# opt2bnc_trigger_1Ch.net
KiCad netlist of a schematic drawn in EAGLE
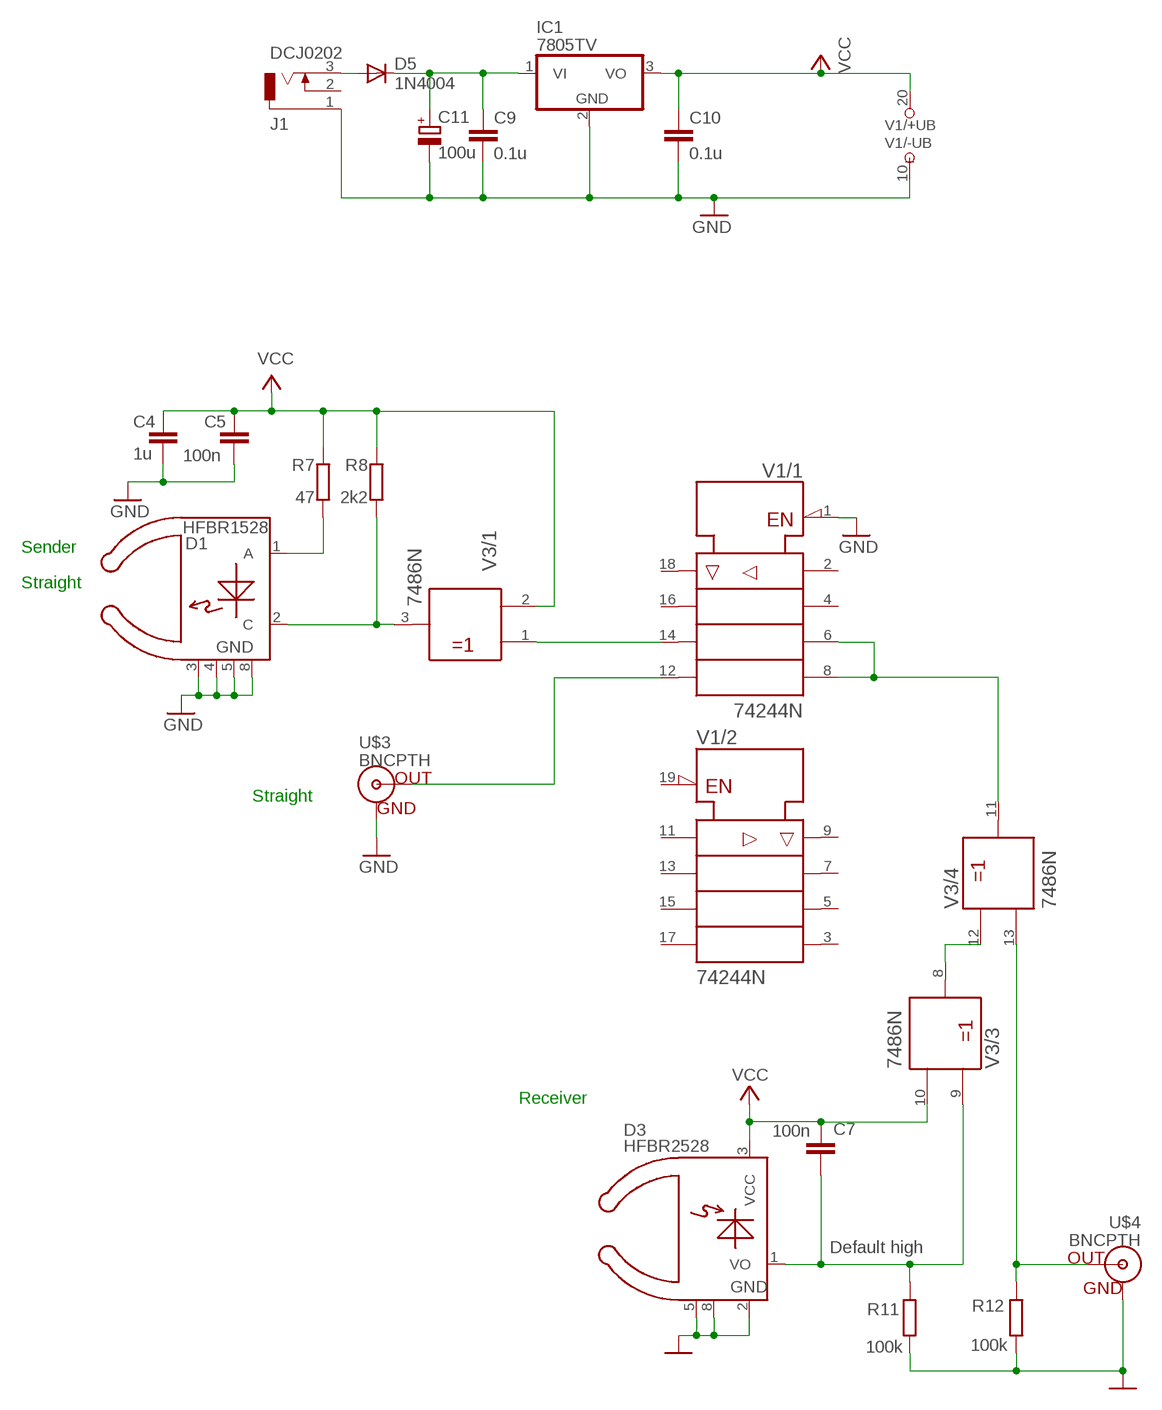
[diagram p0: schematic, sheet 1]

(export (version "E")
  (design (tool "Eeschema 10.0.6"))
  (components
    (comp (ref "C4")
      (value "1u")
      (footprint "eagle-import:C025-025X050")
      (libsource (lib "eagle-import") (part "C-EU025-025X050"))
    )
    (comp (ref "C5")
      (value "100n")
      (footprint "eagle-import:C025-025X050")
      (libsource (lib "eagle-import") (part "C-EU025-025X050"))
    )
    (comp (ref "C7")
      (value "100n")
      (footprint "eagle-import:C025-025X050")
      (libsource (lib "eagle-import") (part "C-EU025-025X050"))
    )
    (comp (ref "C9")
      (value "0.1u")
      (footprint "eagle-import:C025-024X044")
      (libsource (lib "eagle-import") (part "C-EU025-024X044"))
    )
    (comp (ref "C10")
      (value "0.1u")
      (footprint "eagle-import:C025-024X044")
      (libsource (lib "eagle-import") (part "C-EU025-024X044"))
    )
    (comp (ref "C11")
      (value "100u")
      (footprint "eagle-import:E2-4")
      (libsource (lib "eagle-import") (part "CPOL-EUE2-4"))
    )
    (comp (ref "D1")
      (value "HFBR1528")
      (footprint "eagle-import:HFBR25XX")
      (fields (field (name "MF") "AGILENT TECHNOLOGIES") (field (name "MPN") "HFBR-1528"))
      (libsource (lib "eagle-import") (part "HFBR1528"))
    )
    (comp (ref "D3")
      (value "HFBR2528")
      (footprint "eagle-import:HFBR25XX")
      (fields (field (name "MF") "AGILENT TECHNOLOGIES") (field (name "MPN") "HFBR-2528"))
      (libsource (lib "eagle-import") (part "HFBR2528"))
    )
    (comp (ref "D5")
      (value "1N4004")
      (footprint "eagle-import:DO41-10")
      (libsource (lib "eagle-import") (part "1N4004"))
    )
    (comp (ref "IC1")
      (value "7805TV")
      (footprint "eagle-import:TO220V")
      (libsource (lib "eagle-import") (part "78TV05"))
    )
    (comp (ref "J1")
      (value "DCJ0202")
      (footprint "eagle-import:DCJ0202")
      (libsource (lib "eagle-import") (part "DCJ0202"))
    )
    (comp (ref "R7")
      (value "47")
      (footprint "eagle-import:0207_7")
      (libsource (lib "eagle-import") (part "R-EU_0207/7"))
    )
    (comp (ref "R8")
      (value "2k2")
      (footprint "eagle-import:0207_7")
      (libsource (lib "eagle-import") (part "R-EU_0207/7"))
    )
    (comp (ref "R11")
      (value "100k")
      (footprint "eagle-import:0207_7")
      (libsource (lib "eagle-import") (part "R-EU_0207/7"))
    )
    (comp (ref "R12")
      (value "100k")
      (footprint "eagle-import:0207_7")
      (libsource (lib "eagle-import") (part "R-EU_0207/7"))
    )
    (comp (ref "U$3")
      (value "BNCPTH")
      (footprint "eagle-import:BNC")
      (libsource (lib "eagle-import") (part "BNCPTH"))
    )
    (comp (ref "U$4")
      (value "BNCPTH")
      (footprint "eagle-import:BNC")
      (libsource (lib "eagle-import") (part "BNCPTH"))
    )
    (comp (ref "V1")
      (value "74244N")
      (footprint "eagle-import:DIL20")
      (libsource (lib "eagle-import") (part "74244N"))
    )
    (comp (ref "V3")
      (value "7486N")
      (footprint "eagle-import:DIL14")
      (libsource (lib "eagle-import") (part "7486N"))
    )
  )
  (nets
    (net (code "1") (name "GND") (class "Default")
      (node (ref "C10") (pin "2") (pinfunction "2_2") (pintype "passive"))
      (node (ref "C11") (pin "-") (pinfunction "-_-") (pintype "passive"))
      (node (ref "C4") (pin "2") (pinfunction "2_2") (pintype "passive"))
      (node (ref "C5") (pin "2") (pinfunction "2_2") (pintype "passive"))
      (node (ref "C9") (pin "2") (pinfunction "2_2") (pintype "passive"))
      (node (ref "D1") (pin "3") (pinfunction "1_3") (pintype "passive"))
      (node (ref "D1") (pin "4") (pinfunction "4_4") (pintype "passive"))
      (node (ref "D1") (pin "5") (pinfunction "GND_5") (pintype "passive"))
      (node (ref "D1") (pin "8") (pinfunction "GND_8") (pintype "passive"))
      (node (ref "D3") (pin "2") (pinfunction "GND_2") (pintype "passive"))
      (node (ref "D3") (pin "5") (pinfunction "1_5") (pintype "passive"))
      (node (ref "D3") (pin "8") (pinfunction "4_8") (pintype "passive"))
      (node (ref "IC1") (pin "2") (pinfunction "GND_2") (pintype "passive"))
      (node (ref "J1") (pin "1") (pinfunction "1_1") (pintype "passive"))
      (node (ref "R11") (pin "2") (pinfunction "2_2") (pintype "passive"))
      (node (ref "R12") (pin "2") (pinfunction "2_2") (pintype "passive"))
      (node (ref "U$3") (pin "GND") (pinfunction "GND_GND") (pintype "bidirectional"))
      (node (ref "U$4") (pin "GND") (pinfunction "GND_GND") (pintype "bidirectional"))
      (node (ref "V1") (pin "1") (pinfunction "~{G}_1") (pintype "input"))
      (node (ref "V1") (pin "10") (pinfunction "-UB_10") (pintype "power_in"))
    )
    (net (code "2") (name "Net-(D1-A)") (class "Default")
      (node (ref "D1") (pin "1") (pinfunction "A_1") (pintype "passive"))
      (node (ref "R7") (pin "1") (pinfunction "1_1") (pintype "passive"))
    )
    (net (code "3") (name "Net-(D1-C)") (class "Default")
      (node (ref "D1") (pin "2") (pinfunction "C_2") (pintype "passive"))
      (node (ref "R8") (pin "1") (pinfunction "1_1") (pintype "passive"))
      (node (ref "V3") (pin "3") (pinfunction "Y_3") (pintype "output"))
    )
    (net (code "4") (name "Net-(D3-VO)") (class "Default")
      (node (ref "C7") (pin "1") (pinfunction "1_1") (pintype "passive"))
      (node (ref "D3") (pin "1") (pinfunction "VO_1") (pintype "output"))
      (node (ref "R11") (pin "1") (pinfunction "1_1") (pintype "passive"))
      (node (ref "V3") (pin "9") (pinfunction "A_9") (pintype "input"))
    )
    (net (code "5") (name "Net-(D5-PadA)") (class "Default")
      (node (ref "D5") (pin "A") (pinfunction "A_A") (pintype "passive"))
      (node (ref "J1") (pin "3") (pinfunction "3_3") (pintype "passive"))
    )
    (net (code "6") (name "Net-(IC1-VI)") (class "Default")
      (node (ref "C11") (pin "+") (pinfunction "+_+") (pintype "passive"))
      (node (ref "C9") (pin "1") (pinfunction "1_1") (pintype "passive"))
      (node (ref "D5") (pin "C") (pinfunction "C_C") (pintype "passive"))
      (node (ref "IC1") (pin "1") (pinfunction "VI_1") (pintype "input"))
    )
    (net (code "7") (name "Net-(U$3-OUT)") (class "Default")
      (node (ref "U$3") (pin "S") (pinfunction "OUT_S") (pintype "bidirectional"))
      (node (ref "V1") (pin "12") (pinfunction "Y4_12") (pintype "tri_state"))
    )
    (net (code "8") (name "Net-(U$4-OUT)") (class "Default")
      (node (ref "R12") (pin "1") (pinfunction "1_1") (pintype "passive"))
      (node (ref "U$4") (pin "S") (pinfunction "OUT_S") (pintype "bidirectional"))
      (node (ref "V3") (pin "13") (pinfunction "B_13") (pintype "input"))
    )
    (net (code "9") (name "Net-(V1C-A3)") (class "Default")
      (node (ref "V1") (pin "6") (pinfunction "A3_6") (pintype "input"))
      (node (ref "V1") (pin "8") (pinfunction "A4_8") (pintype "input"))
      (node (ref "V3") (pin "11") (pinfunction "Y_11") (pintype "output"))
    )
    (net (code "10") (name "Net-(V1C-Y3)") (class "Default")
      (node (ref "V1") (pin "14") (pinfunction "Y3_14") (pintype "tri_state"))
      (node (ref "V3") (pin "1") (pinfunction "A_1") (pintype "input"))
    )
    (net (code "11") (name "Net-(V3E-Y)") (class "Default")
      (node (ref "V3") (pin "12") (pinfunction "A_12") (pintype "input"))
      (node (ref "V3") (pin "8") (pinfunction "Y_8") (pintype "output"))
    )
    (net (code "12") (name "VCC") (class "Default")
      (node (ref "C10") (pin "1") (pinfunction "1_1") (pintype "passive"))
      (node (ref "C4") (pin "1") (pinfunction "1_1") (pintype "passive"))
      (node (ref "C5") (pin "1") (pinfunction "1_1") (pintype "passive"))
      (node (ref "C7") (pin "2") (pinfunction "2_2") (pintype "passive"))
      (node (ref "D3") (pin "3") (pinfunction "VCC_3") (pintype "passive"))
      (node (ref "IC1") (pin "3") (pinfunction "VO_3") (pintype "passive"))
      (node (ref "R7") (pin "2") (pinfunction "2_2") (pintype "passive"))
      (node (ref "R8") (pin "2") (pinfunction "2_2") (pintype "passive"))
      (node (ref "V1") (pin "20") (pinfunction "+UB_20") (pintype "power_in"))
      (node (ref "V3") (pin "10") (pinfunction "B_10") (pintype "input"))
      (node (ref "V3") (pin "2") (pinfunction "B_2") (pintype "input"))
    )
    (net (code "13") (name "unconnected-(J1-Pad2)") (class "Default")
      (node (ref "J1") (pin "2") (pinfunction "2_2") (pintype "passive"))
    )
    (net (code "14") (name "unconnected-(V1C-A1-Pad2)") (class "Default")
      (node (ref "V1") (pin "2") (pinfunction "A1_2") (pintype "input"))
    )
    (net (code "15") (name "unconnected-(V1C-A2-Pad4)") (class "Default")
      (node (ref "V1") (pin "4") (pinfunction "A2_4") (pintype "input"))
    )
    (net (code "16") (name "unconnected-(V1C-Y1-Pad18)") (class "Default")
      (node (ref "V1") (pin "18") (pinfunction "Y1_18") (pintype "tri_state"))
    )
    (net (code "17") (name "unconnected-(V1C-Y2-Pad16)") (class "Default")
      (node (ref "V1") (pin "16") (pinfunction "Y2_16") (pintype "tri_state"))
    )
    (net (code "18") (name "unconnected-(V1D-A1-Pad11)") (class "Default")
      (node (ref "V1") (pin "11") (pinfunction "A1_11") (pintype "input"))
    )
    (net (code "19") (name "unconnected-(V1D-A2-Pad13)") (class "Default")
      (node (ref "V1") (pin "13") (pinfunction "A2_13") (pintype "input"))
    )
    (net (code "20") (name "unconnected-(V1D-A3-Pad15)") (class "Default")
      (node (ref "V1") (pin "15") (pinfunction "A3_15") (pintype "input"))
    )
    (net (code "21") (name "unconnected-(V1D-A4-Pad17)") (class "Default")
      (node (ref "V1") (pin "17") (pinfunction "A4_17") (pintype "input"))
    )
    (net (code "22") (name "unconnected-(V1D-Y1-Pad9)") (class "Default")
      (node (ref "V1") (pin "9") (pinfunction "Y1_9") (pintype "tri_state"))
    )
    (net (code "23") (name "unconnected-(V1D-Y2-Pad7)") (class "Default")
      (node (ref "V1") (pin "7") (pinfunction "Y2_7") (pintype "tri_state"))
    )
    (net (code "24") (name "unconnected-(V1D-Y3-Pad5)") (class "Default")
      (node (ref "V1") (pin "5") (pinfunction "Y3_5") (pintype "tri_state"))
    )
    (net (code "25") (name "unconnected-(V1D-Y4-Pad3)") (class "Default")
      (node (ref "V1") (pin "3") (pinfunction "Y4_3") (pintype "tri_state"))
    )
    (net (code "26") (name "unconnected-(V1D-~{G}-Pad19)") (class "Default")
      (node (ref "V1") (pin "19") (pinfunction "~{G}_19") (pintype "input"))
    )
  )
)
